# Power_supplies_V2.net
KiCad netlist of a schematic drawn in Altium Designer
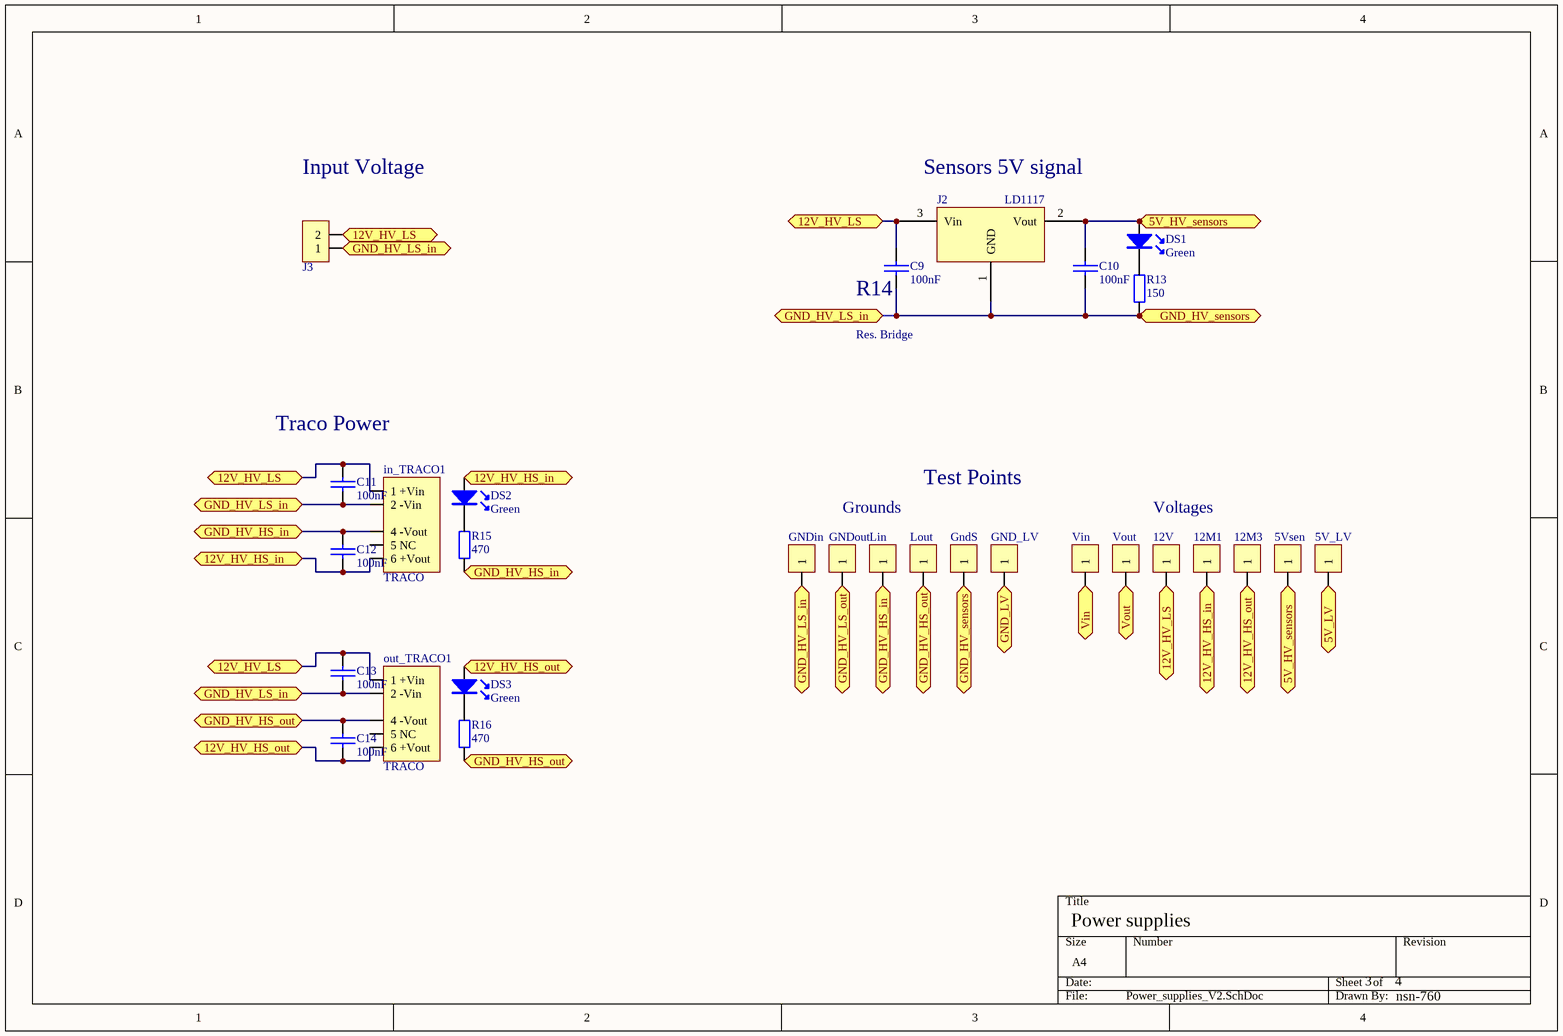
[diagram p0: Power_supplies_V2.SchDoc]

(export (version "E")
  (design (tool "Eeschema 10.0.6"))
  (components
    (comp (ref "5Vsen")
      (value "Test Point")
      (footprint "Test_Point")
      (libsource (lib "SCH_Lib") (part "Test Point"))
    )
    (comp (ref "5V_LV")
      (value "Test Point")
      (footprint "Test_Point")
      (libsource (lib "SCH_Lib") (part "Test Point"))
    )
    (comp (ref "12M1")
      (value "Test Point")
      (footprint "Test_Point")
      (libsource (lib "SCH_Lib") (part "Test Point"))
    )
    (comp (ref "12M3")
      (value "Test Point")
      (footprint "Test_Point")
      (libsource (lib "SCH_Lib") (part "Test Point"))
    )
    (comp (ref "12V")
      (value "Test Point")
      (footprint "Test_Point")
      (libsource (lib "SCH_Lib") (part "Test Point"))
    )
    (comp (ref "C9")
      (value "100nF")
      (footprint "1206")
      (description "Condensador")
      (libsource (lib "SCH_Lib") (part "Condensador"))
    )
    (comp (ref "C10")
      (value "100nF")
      (footprint "1206")
      (description "Condensador")
      (libsource (lib "SCH_Lib") (part "Condensador"))
    )
    (comp (ref "C11")
      (value "100nF")
      (footprint "1206")
      (description "Condensador")
      (libsource (lib "SCH_Lib") (part "Condensador"))
    )
    (comp (ref "C12")
      (value "100nF")
      (footprint "1206")
      (description "Condensador")
      (libsource (lib "SCH_Lib") (part "Condensador"))
    )
    (comp (ref "C13")
      (value "100nF")
      (footprint "1206")
      (description "Condensador")
      (libsource (lib "SCH_Lib") (part "Condensador"))
    )
    (comp (ref "C14")
      (value "100nF")
      (footprint "1206")
      (description "Condensador")
      (libsource (lib "SCH_Lib") (part "Condensador"))
    )
    (comp (ref "DS1") (value "Green") (footprint "Led 2.2mm") (libsource (lib "SCH_Lib") (part "Led")))
    (comp (ref "DS2") (value "Green") (footprint "Led 2.2mm") (libsource (lib "SCH_Lib") (part "Led")))
    (comp (ref "DS3") (value "Green") (footprint "Led 2.2mm") (libsource (lib "SCH_Lib") (part "Led")))
    (comp (ref "GNDin")
      (value "Test Point")
      (footprint "Test_Point")
      (libsource (lib "SCH_Lib") (part "Test Point"))
    )
    (comp (ref "GNDout")
      (value "Test Point")
      (footprint "Test_Point")
      (libsource (lib "SCH_Lib") (part "Test Point"))
    )
    (comp (ref "GndS")
      (value "Test Point")
      (footprint "Test_Point")
      (libsource (lib "SCH_Lib") (part "Test Point"))
    )
    (comp (ref "GND_LV")
      (value "Test Point")
      (footprint "Test_Point")
      (libsource (lib "SCH_Lib") (part "Test Point"))
    )
    (comp (ref "in_TRACO1")
      (value "TRACO")
      (footprint "TRACO_TMA1212S")
      (description "TracoPower TMA1212S")
      (libsource (lib "SCH_Lib") (part "TRACO"))
    )
    (comp (ref "J2")
      (value "LD1117")
      (footprint "SOT-223_LM1117")
      (description "Linear voltage regulator")
      (libsource (lib "SCH_Lib") (part "LD1117"))
    )
    (comp (ref "J3")
      (value "Cleva 2 vias")
      (footprint "Con2_Extron _3.5mmPitch")
      (libsource (lib "SCH_Lib") (part "Con_2"))
    )
    (comp (ref "Lin")
      (value "Test Point")
      (footprint "Test_Point")
      (libsource (lib "SCH_Lib") (part "Test Point"))
    )
    (comp (ref "Lout")
      (value "Test Point")
      (footprint "Test_Point")
      (libsource (lib "SCH_Lib") (part "Test Point"))
    )
    (comp (ref "out_TRACO1")
      (value "TRACO")
      (footprint "TRACO_TMA1212S")
      (description "TracoPower TMA1212S")
      (libsource (lib "SCH_Lib") (part "TRACO"))
    )
    (comp (ref "R13")
      (value "150")
      (footprint "1206")
      (description "Resistencia")
      (libsource (lib "SCH_Lib") (part "Resistencia"))
    )
    (comp (ref "R14")
      (value "Res. Bridge")
      (footprint "1206")
      (description "Resistencia Bridge")
      (libsource (lib "SCH_Lib") (part "Res. Bridge"))
    )
    (comp (ref "R15")
      (value "470")
      (footprint "1206")
      (description "Resistencia")
      (libsource (lib "SCH_Lib") (part "Resistencia"))
    )
    (comp (ref "R16")
      (value "470")
      (footprint "1206")
      (description "Resistencia")
      (libsource (lib "SCH_Lib") (part "Resistencia"))
    )
    (comp (ref "Vin")
      (value "Test Point")
      (footprint "Test_Point")
      (libsource (lib "SCH_Lib") (part "Test Point"))
    )
    (comp (ref "Vout")
      (value "Test Point")
      (footprint "Test_Point")
      (libsource (lib "SCH_Lib") (part "Test Point"))
    )
  )
  (nets
    (net (code "1") (name "/5V_HV_sensors") (class "Default")
      (node (ref "5Vsen") (pin "1") (pinfunction "1_1") (pintype "passive"))
      (node (ref "C10") (pin "2") (pintype "passive"))
      (node (ref "DS1") (pin "A") (pinfunction "A_A") (pintype "passive"))
      (node (ref "J2") (pin "2") (pinfunction "Vout_2") (pintype "passive"))
    )
    (net (code "2") (name "/5V_LV") (class "Default")
      (node (ref "5V_LV") (pin "1") (pinfunction "1_1") (pintype "passive"))
    )
    (net (code "3") (name "/12V_HV_HS_in") (class "Default")
      (node (ref "12M1") (pin "1") (pinfunction "1_1") (pintype "passive"))
      (node (ref "C12") (pin "1") (pintype "passive"))
      (node (ref "DS2") (pin "A") (pinfunction "A_A") (pintype "passive"))
      (node (ref "in_TRACO1") (pin "6") (pinfunction "6_+Vout_6") (pintype "passive"))
    )
    (net (code "4") (name "/12V_HV_HS_out") (class "Default")
      (node (ref "12M3") (pin "1") (pinfunction "1_1") (pintype "passive"))
      (node (ref "C14") (pin "1") (pintype "passive"))
      (node (ref "DS3") (pin "A") (pinfunction "A_A") (pintype "passive"))
      (node (ref "out_TRACO1") (pin "6") (pinfunction "6_+Vout_6") (pintype "passive"))
    )
    (net (code "5") (name "/12V_HV_LS") (class "Default")
      (node (ref "12V") (pin "1") (pinfunction "1_1") (pintype "passive"))
      (node (ref "C11") (pin "2") (pintype "passive"))
      (node (ref "C13") (pin "2") (pintype "passive"))
      (node (ref "C9") (pin "2") (pintype "passive"))
      (node (ref "J2") (pin "3") (pinfunction "Vin_3") (pintype "passive"))
      (node (ref "J3") (pin "2") (pinfunction "2_2") (pintype "passive"))
      (node (ref "in_TRACO1") (pin "1") (pinfunction "1_+Vin_1") (pintype "passive"))
      (node (ref "out_TRACO1") (pin "1") (pinfunction "1_+Vin_1") (pintype "passive"))
    )
    (net (code "6") (name "/GND_HV_HS_in") (class "Default")
      (node (ref "C12") (pin "2") (pintype "passive"))
      (node (ref "Lin") (pin "1") (pinfunction "1_1") (pintype "passive"))
      (node (ref "R15") (pin "2") (pinfunction "2_2") (pintype "passive"))
      (node (ref "in_TRACO1") (pin "4") (pinfunction "4_-Vout_4") (pintype "passive"))
    )
    (net (code "7") (name "/GND_HV_HS_out") (class "Default")
      (node (ref "C14") (pin "2") (pintype "passive"))
      (node (ref "Lout") (pin "1") (pinfunction "1_1") (pintype "passive"))
      (node (ref "R16") (pin "2") (pinfunction "2_2") (pintype "passive"))
      (node (ref "out_TRACO1") (pin "4") (pinfunction "4_-Vout_4") (pintype "passive"))
    )
    (net (code "8") (name "/GND_HV_LS_in") (class "Default")
      (node (ref "C11") (pin "1") (pintype "passive"))
      (node (ref "C13") (pin "1") (pintype "passive"))
      (node (ref "GNDin") (pin "1") (pinfunction "1_1") (pintype "passive"))
      (node (ref "J3") (pin "1") (pinfunction "1_1") (pintype "passive"))
      (node (ref "R14") (pin "1") (pinfunction "1_1") (pintype "passive"))
      (node (ref "in_TRACO1") (pin "2") (pinfunction "2_-Vin_2") (pintype "passive"))
      (node (ref "out_TRACO1") (pin "2") (pinfunction "2_-Vin_2") (pintype "passive"))
    )
    (net (code "9") (name "/GND_HV_LS_out") (class "Default")
      (node (ref "GNDout") (pin "1") (pinfunction "1_1") (pintype "passive"))
    )
    (net (code "10") (name "/GND_HV_sensors") (class "Default")
      (node (ref "C10") (pin "1") (pintype "passive"))
      (node (ref "C9") (pin "1") (pintype "passive"))
      (node (ref "GndS") (pin "1") (pinfunction "1_1") (pintype "passive"))
      (node (ref "J2") (pin "1") (pinfunction "GND_1") (pintype "passive"))
      (node (ref "R13") (pin "2") (pinfunction "2_2") (pintype "passive"))
      (node (ref "R14") (pin "2") (pinfunction "2_2") (pintype "passive"))
    )
    (net (code "11") (name "/GND_LV") (class "Default")
      (node (ref "GND_LV") (pin "1") (pinfunction "1_1") (pintype "passive"))
    )
    (net (code "12") (name "/Vin") (class "Default")
      (node (ref "Vin") (pin "1") (pinfunction "1_1") (pintype "passive"))
    )
    (net (code "13") (name "/Vout") (class "Default")
      (node (ref "Vout") (pin "1") (pinfunction "1_1") (pintype "passive"))
    )
    (net (code "14") (name "Net-(DS1-PadK)") (class "Default")
      (node (ref "DS1") (pin "K") (pinfunction "K_K") (pintype "passive"))
      (node (ref "R13") (pin "1") (pinfunction "1_1") (pintype "passive"))
    )
    (net (code "15") (name "Net-(DS2-PadK)") (class "Default")
      (node (ref "DS2") (pin "K") (pinfunction "K_K") (pintype "passive"))
      (node (ref "R15") (pin "1") (pinfunction "1_1") (pintype "passive"))
    )
    (net (code "16") (name "Net-(DS3-PadK)") (class "Default")
      (node (ref "DS3") (pin "K") (pinfunction "K_K") (pintype "passive"))
      (node (ref "R16") (pin "1") (pinfunction "1_1") (pintype "passive"))
    )
    (net (code "17") (name "unconnected-(in_TRACO1-5_NC-Pad5)") (class "Default")
      (node (ref "in_TRACO1") (pin "5") (pinfunction "5_NC_5") (pintype "passive"))
    )
    (net (code "18") (name "unconnected-(out_TRACO1-5_NC-Pad5)") (class "Default")
      (node (ref "out_TRACO1") (pin "5") (pinfunction "5_NC_5") (pintype "passive"))
    )
  )
)
